# OCC_Test-_RailCom.net
KiCad netlist of a schematic drawn in EasyEDA
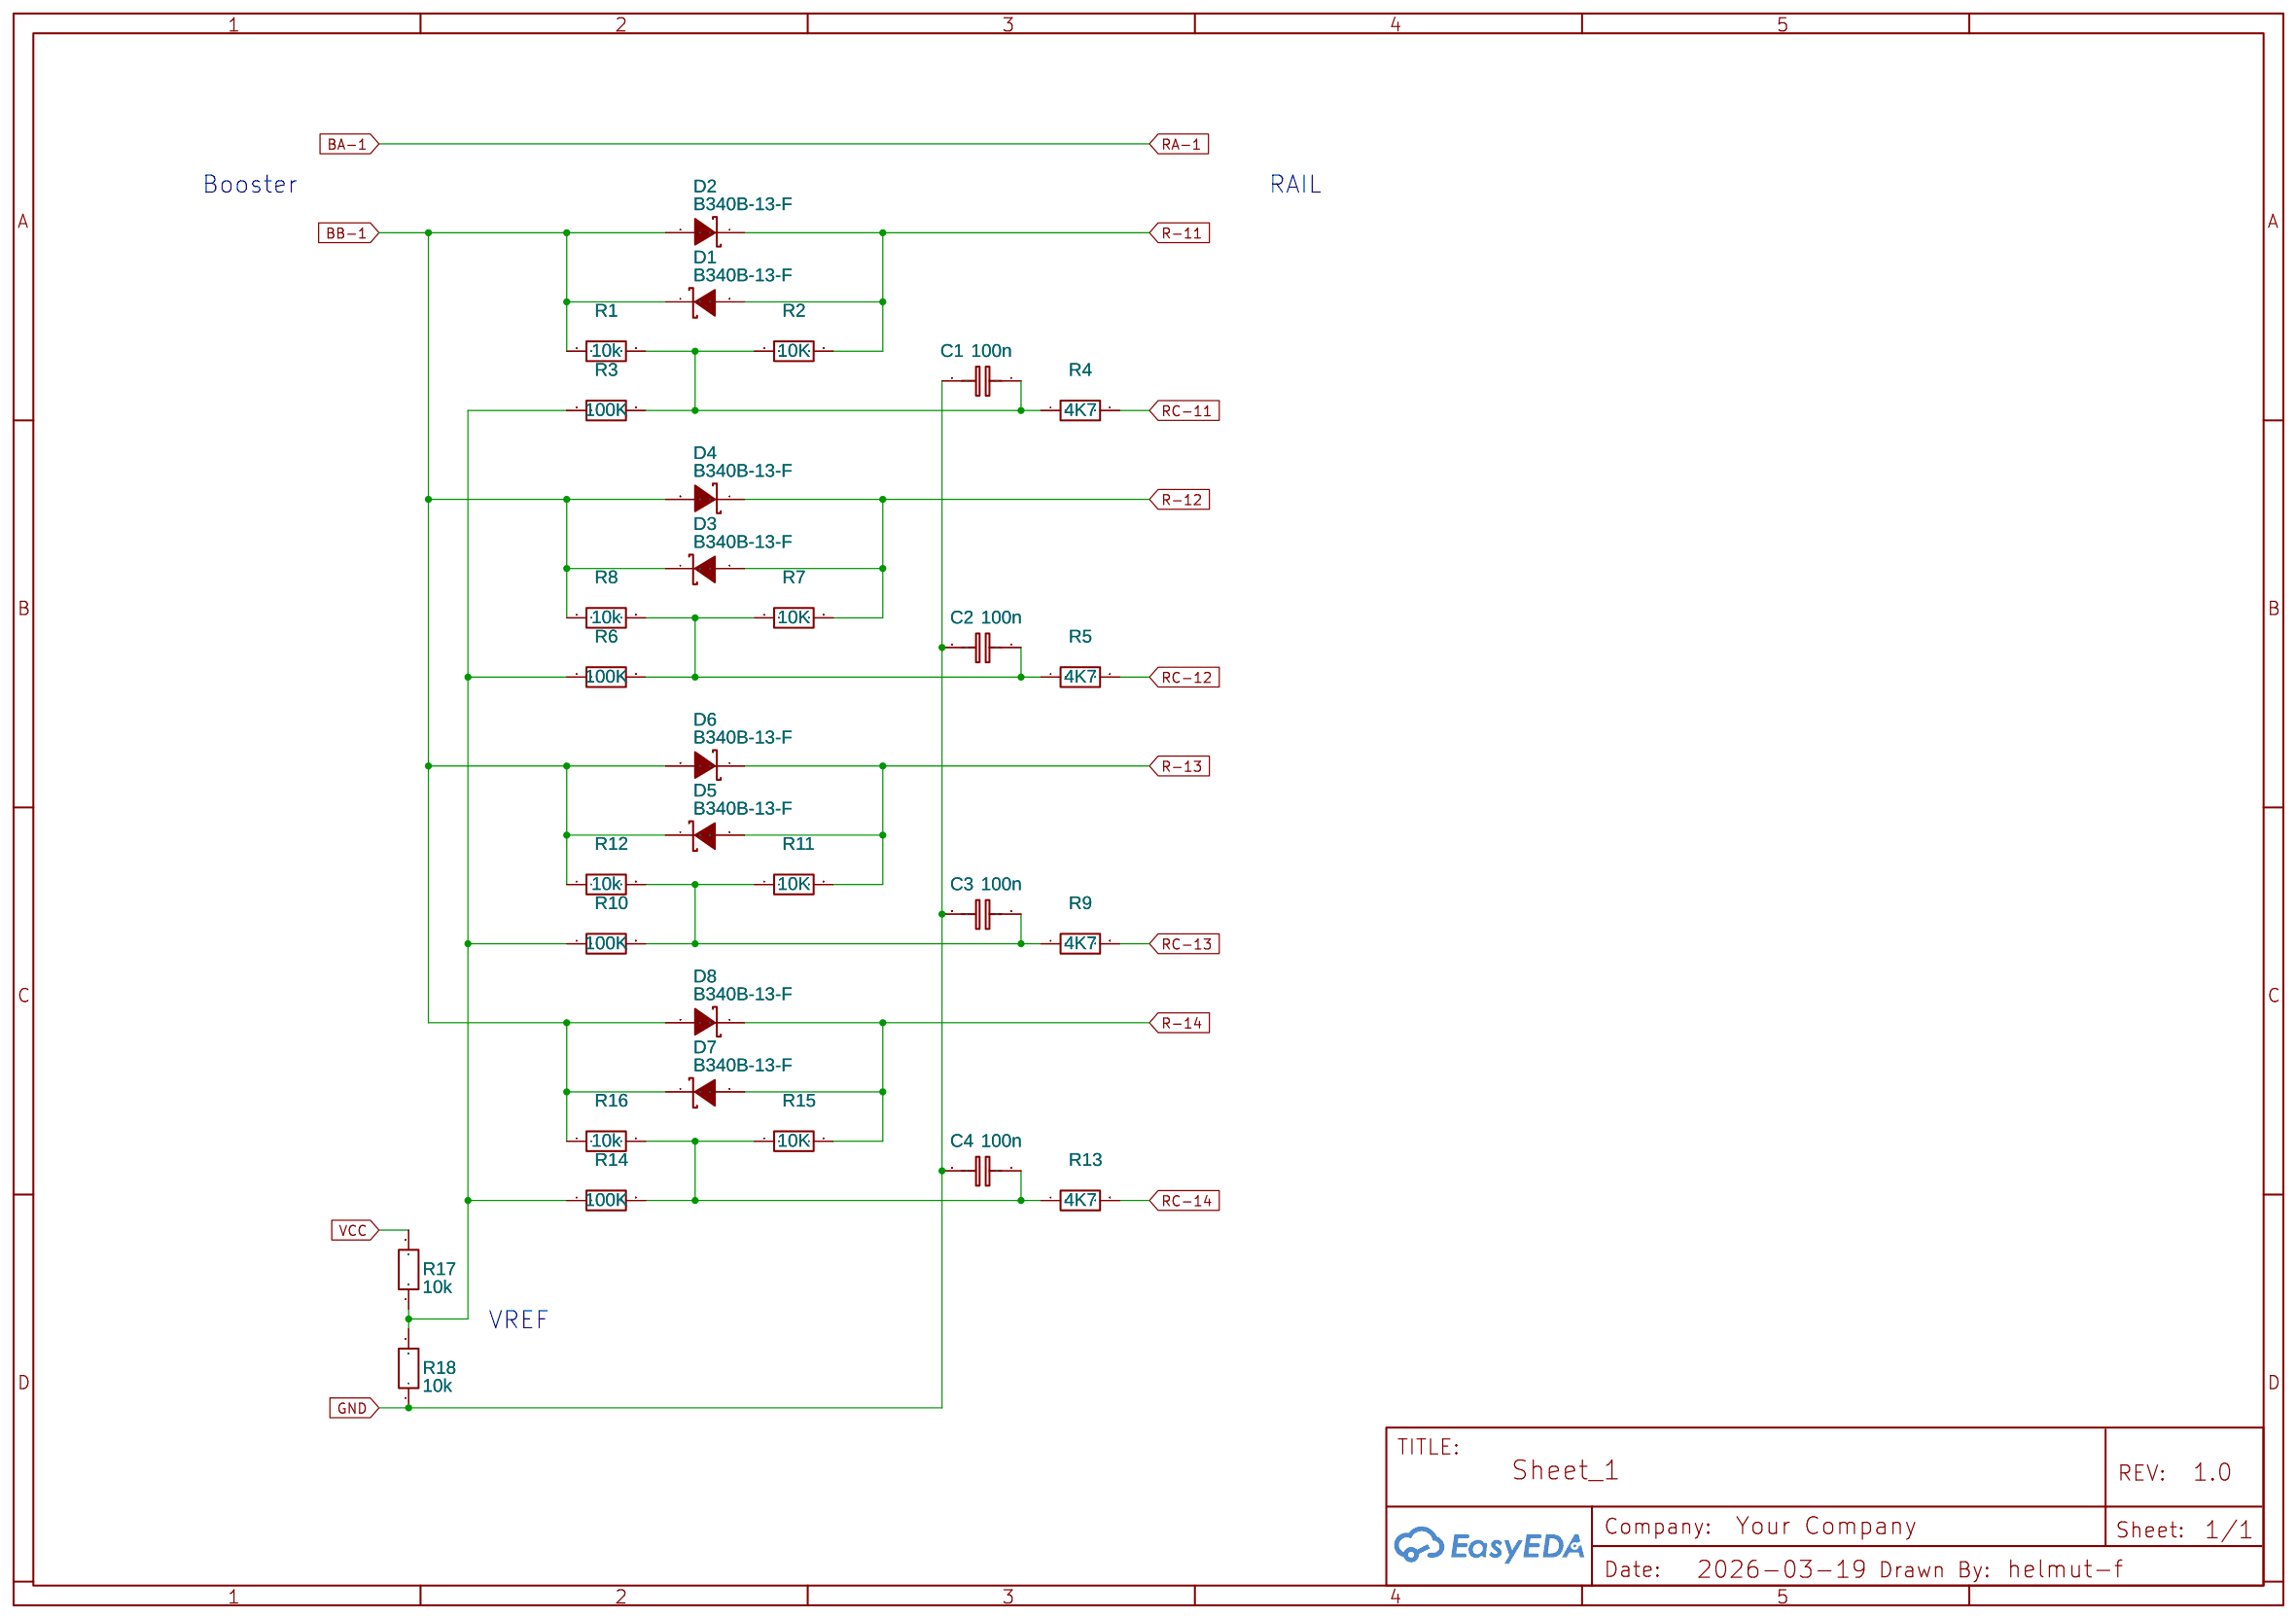
[diagram p0: schematic sheet]

(export (version "E")
  (design (tool "Eeschema 10.0.6"))
  (components
    (comp (ref "C1") (value "100n") (libsource (lib "") (part "C_1206_EU_1")))
    (comp (ref "C2") (value "100n") (libsource (lib "") (part "C_1206_EU")))
    (comp (ref "C3") (value "100n") (libsource (lib "") (part "C_1206_EU")))
    (comp (ref "C4") (value "100n") (libsource (lib "") (part "C_1206_EU")))
    (comp (ref "D1")
      (value "B340B-13-F")
      (fields (field (name "Manufacturer") "DIODES(美台)"))
      (libsource (lib "") (part "B340B-13-F_1"))
    )
    (comp (ref "D2")
      (value "B340B-13-F")
      (fields (field (name "Manufacturer") "DIODES(美台)"))
      (libsource (lib "") (part "B340B-13-F"))
    )
    (comp (ref "D3")
      (value "B340B-13-F")
      (fields (field (name "Manufacturer") "DIODES(美台)"))
      (libsource (lib "") (part "B340B-13-F_1"))
    )
    (comp (ref "D4")
      (value "B340B-13-F")
      (fields (field (name "Manufacturer") "DIODES(美台)"))
      (libsource (lib "") (part "B340B-13-F"))
    )
    (comp (ref "D5")
      (value "B340B-13-F")
      (fields (field (name "Manufacturer") "DIODES(美台)"))
      (libsource (lib "") (part "B340B-13-F_1"))
    )
    (comp (ref "D6")
      (value "B340B-13-F")
      (fields (field (name "Manufacturer") "DIODES(美台)"))
      (libsource (lib "") (part "B340B-13-F"))
    )
    (comp (ref "D7")
      (value "B340B-13-F")
      (fields (field (name "Manufacturer") "DIODES(美台)"))
      (libsource (lib "") (part "B340B-13-F_1"))
    )
    (comp (ref "D8")
      (value "B340B-13-F")
      (fields (field (name "Manufacturer") "DIODES(美台)"))
      (libsource (lib "") (part "B340B-13-F"))
    )
    (comp (ref "R1") (value "10k") (libsource (lib "") (part "R_1206_EU")))
    (comp (ref "R2") (value "10K") (libsource (lib "") (part "R_1206_EU")))
    (comp (ref "R3") (value "100K") (libsource (lib "") (part "R_1206_EU")))
    (comp (ref "R4") (value "4K7") (libsource (lib "") (part "R_1206_EU")))
    (comp (ref "R5") (value "4K7") (libsource (lib "") (part "R_1206_EU")))
    (comp (ref "R6") (value "100K") (libsource (lib "") (part "R_1206_EU")))
    (comp (ref "R7") (value "10K") (libsource (lib "") (part "R_1206_EU")))
    (comp (ref "R8") (value "10k") (libsource (lib "") (part "R_1206_EU")))
    (comp (ref "R9") (value "4K7") (libsource (lib "") (part "R_1206_EU")))
    (comp (ref "R10") (value "100K") (libsource (lib "") (part "R_1206_EU")))
    (comp (ref "R11") (value "10K") (libsource (lib "") (part "R_1206_EU")))
    (comp (ref "R12") (value "10k") (libsource (lib "") (part "R_1206_EU")))
    (comp (ref "R13") (value "4K7") (libsource (lib "") (part "R_1206_EU")))
    (comp (ref "R14") (value "100K") (libsource (lib "") (part "R_1206_EU")))
    (comp (ref "R15") (value "10K") (libsource (lib "") (part "R_1206_EU")))
    (comp (ref "R16") (value "10k") (libsource (lib "") (part "R_1206_EU")))
    (comp (ref "R17") (value "10k") (libsource (lib "") (part "R_1206_EU_1")))
    (comp (ref "R18") (value "10k") (libsource (lib "") (part "R_1206_EU_1")))
  )
  (nets
    (net (code "2") (name "BB-1") (class "Default")
      (node (ref "D1") (pin "1") (pinfunction "K_1") (pintype "unspecified"))
      (node (ref "D2") (pin "2") (pinfunction "A_2") (pintype "unspecified"))
      (node (ref "D3") (pin "1") (pinfunction "K_1") (pintype "unspecified"))
      (node (ref "D4") (pin "2") (pinfunction "A_2") (pintype "unspecified"))
      (node (ref "D5") (pin "1") (pinfunction "K_1") (pintype "unspecified"))
      (node (ref "D6") (pin "2") (pinfunction "A_2") (pintype "unspecified"))
      (node (ref "D7") (pin "1") (pinfunction "K_1") (pintype "unspecified"))
      (node (ref "D8") (pin "2") (pinfunction "A_2") (pintype "unspecified"))
      (node (ref "R1") (pin "1") (pinfunction "1_1") (pintype "unspecified"))
      (node (ref "R12") (pin "1") (pinfunction "1_1") (pintype "unspecified"))
      (node (ref "R16") (pin "1") (pinfunction "1_1") (pintype "unspecified"))
      (node (ref "R8") (pin "1") (pinfunction "1_1") (pintype "unspecified"))
    )
    (net (code "3") (name "GND") (class "Default")
      (node (ref "C1") (pin "2") (pinfunction "2_2") (pintype "unspecified"))
      (node (ref "C2") (pin "2") (pinfunction "2_2") (pintype "unspecified"))
      (node (ref "C3") (pin "2") (pinfunction "2_2") (pintype "unspecified"))
      (node (ref "C4") (pin "2") (pinfunction "2_2") (pintype "unspecified"))
      (node (ref "R18") (pin "1") (pinfunction "1_1") (pintype "unspecified"))
    )
    (net (code "4") (name "Net-(C1-Pad1)") (class "Default")
      (node (ref "C1") (pin "1") (pinfunction "1_1") (pintype "unspecified"))
      (node (ref "R1") (pin "2") (pinfunction "2_2") (pintype "unspecified"))
      (node (ref "R2") (pin "1") (pinfunction "1_1") (pintype "unspecified"))
      (node (ref "R3") (pin "2") (pinfunction "2_2") (pintype "unspecified"))
      (node (ref "R4") (pin "1") (pinfunction "1_1") (pintype "unspecified"))
    )
    (net (code "5") (name "Net-(C2-Pad1)") (class "Default")
      (node (ref "C2") (pin "1") (pinfunction "1_1") (pintype "unspecified"))
      (node (ref "R5") (pin "1") (pinfunction "1_1") (pintype "unspecified"))
      (node (ref "R6") (pin "2") (pinfunction "2_2") (pintype "unspecified"))
      (node (ref "R7") (pin "1") (pinfunction "1_1") (pintype "unspecified"))
      (node (ref "R8") (pin "2") (pinfunction "2_2") (pintype "unspecified"))
    )
    (net (code "6") (name "Net-(C3-Pad1)") (class "Default")
      (node (ref "C3") (pin "1") (pinfunction "1_1") (pintype "unspecified"))
      (node (ref "R10") (pin "2") (pinfunction "2_2") (pintype "unspecified"))
      (node (ref "R11") (pin "1") (pinfunction "1_1") (pintype "unspecified"))
      (node (ref "R12") (pin "2") (pinfunction "2_2") (pintype "unspecified"))
      (node (ref "R9") (pin "1") (pinfunction "1_1") (pintype "unspecified"))
    )
    (net (code "7") (name "Net-(C4-Pad1)") (class "Default")
      (node (ref "C4") (pin "1") (pinfunction "1_1") (pintype "unspecified"))
      (node (ref "R13") (pin "1") (pinfunction "1_1") (pintype "unspecified"))
      (node (ref "R14") (pin "2") (pinfunction "2_2") (pintype "unspecified"))
      (node (ref "R15") (pin "1") (pinfunction "1_1") (pintype "unspecified"))
      (node (ref "R16") (pin "2") (pinfunction "2_2") (pintype "unspecified"))
    )
    (net (code "8") (name "Net-(R10-Pad1)") (class "Default")
      (node (ref "R10") (pin "1") (pinfunction "1_1") (pintype "unspecified"))
      (node (ref "R14") (pin "1") (pinfunction "1_1") (pintype "unspecified"))
      (node (ref "R17") (pin "1") (pinfunction "1_1") (pintype "unspecified"))
      (node (ref "R18") (pin "2") (pinfunction "2_2") (pintype "unspecified"))
      (node (ref "R3") (pin "1") (pinfunction "1_1") (pintype "unspecified"))
      (node (ref "R6") (pin "1") (pinfunction "1_1") (pintype "unspecified"))
    )
    (net (code "9") (name "R-11") (class "Default")
      (node (ref "D1") (pin "2") (pinfunction "A_2") (pintype "unspecified"))
      (node (ref "D2") (pin "1") (pinfunction "K_1") (pintype "unspecified"))
      (node (ref "R2") (pin "2") (pinfunction "2_2") (pintype "unspecified"))
    )
    (net (code "10") (name "R-12") (class "Default")
      (node (ref "D3") (pin "2") (pinfunction "A_2") (pintype "unspecified"))
      (node (ref "D4") (pin "1") (pinfunction "K_1") (pintype "unspecified"))
      (node (ref "R7") (pin "2") (pinfunction "2_2") (pintype "unspecified"))
    )
    (net (code "11") (name "R-13") (class "Default")
      (node (ref "D5") (pin "2") (pinfunction "A_2") (pintype "unspecified"))
      (node (ref "D6") (pin "1") (pinfunction "K_1") (pintype "unspecified"))
      (node (ref "R11") (pin "2") (pinfunction "2_2") (pintype "unspecified"))
    )
    (net (code "12") (name "R-14") (class "Default")
      (node (ref "D7") (pin "2") (pinfunction "A_2") (pintype "unspecified"))
      (node (ref "D8") (pin "1") (pinfunction "K_1") (pintype "unspecified"))
      (node (ref "R15") (pin "2") (pinfunction "2_2") (pintype "unspecified"))
    )
    (net (code "13") (name "RC-11") (class "Default")
      (node (ref "R4") (pin "2") (pinfunction "2_2") (pintype "unspecified"))
    )
    (net (code "14") (name "RC-12") (class "Default")
      (node (ref "R5") (pin "2") (pinfunction "2_2") (pintype "unspecified"))
    )
    (net (code "15") (name "RC-13") (class "Default")
      (node (ref "R9") (pin "2") (pinfunction "2_2") (pintype "unspecified"))
    )
    (net (code "16") (name "RC-14") (class "Default")
      (node (ref "R13") (pin "2") (pinfunction "2_2") (pintype "unspecified"))
    )
    (net (code "17") (name "VCC") (class "Default")
      (node (ref "R17") (pin "2") (pinfunction "2_2") (pintype "unspecified"))
    )
  )
)
